# Power_supply.net
KiCad netlist of a schematic drawn in Altium Designer
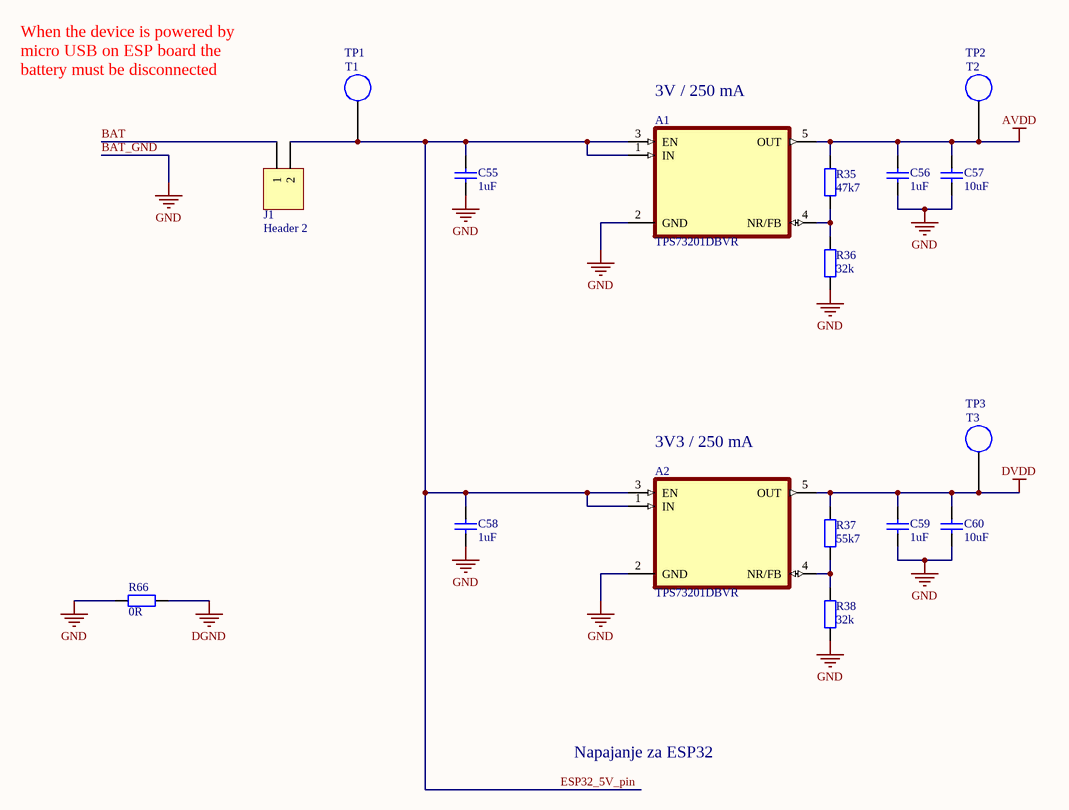
[diagram p0: Power supply.SchDoc]

(export (version "E")
  (design (tool "Eeschema 10.0.6"))
  (components
    (comp (ref "A1")
      (value "TPS73201DBVR")
      (footprint "SOT95P280X145-5N")
      (fields (field (name "MF") "Texas Instruments"))
      (libsource (lib "TPS73201DBVR") (part "TPS73201DBVR"))
    )
    (comp (ref "A2")
      (value "TPS73201DBVR")
      (footprint "SOT95P280X145-5N")
      (fields (field (name "MF") "Texas Instruments"))
      (libsource (lib "TPS73201DBVR") (part "TPS73201DBVR"))
    )
    (comp (ref "C55")
      (value "1uF")
      (footprint "C0603")
      (description "Capacitor")
      (fields (field (name "PUBLISHER") "Altium Limited"))
      (libsource (lib "Miscellaneous Devices") (part "Cap"))
    )
    (comp (ref "C56")
      (value "1uF")
      (footprint "C0603")
      (description "Capacitor")
      (fields (field (name "PUBLISHER") "Altium Limited"))
      (libsource (lib "Miscellaneous Devices") (part "Cap"))
    )
    (comp (ref "C57")
      (value "10uF")
      (footprint "C0603")
      (description "Capacitor")
      (fields (field (name "PUBLISHER") "Altium Limited"))
      (libsource (lib "Miscellaneous Devices") (part "Cap"))
    )
    (comp (ref "C58")
      (value "1uF")
      (footprint "C0603")
      (description "Capacitor")
      (fields (field (name "PUBLISHER") "Altium Limited"))
      (libsource (lib "Miscellaneous Devices") (part "Cap"))
    )
    (comp (ref "C59")
      (value "1uF")
      (footprint "C0603")
      (description "Capacitor")
      (fields (field (name "PUBLISHER") "Altium Limited"))
      (libsource (lib "Miscellaneous Devices") (part "Cap"))
    )
    (comp (ref "C60")
      (value "10uF")
      (footprint "C0603")
      (description "Capacitor")
      (fields (field (name "PUBLISHER") "Altium Limited"))
      (libsource (lib "Miscellaneous Devices") (part "Cap"))
    )
    (comp (ref "J1")
      (value "Header 2")
      (footprint "HDR1X2")
      (description "Header, 2-Pin")
      (fields (field (name "PUBLISHER") "Altium Limited"))
      (libsource (lib "Miscellaneous Connectors") (part "Header 2"))
    )
    (comp (ref "R35")
      (value "47k7")
      (footprint "RES0603")
      (description "Resistor")
      (fields (field (name "PUBLISHER") "Altium Limited"))
      (libsource (lib "Miscellaneous Devices") (part "Res2"))
    )
    (comp (ref "R36")
      (value "32k")
      (footprint "RES0603")
      (description "Resistor")
      (fields (field (name "PUBLISHER") "Altium Limited"))
      (libsource (lib "Miscellaneous Devices") (part "Res2"))
    )
    (comp (ref "R37")
      (value "55k7")
      (footprint "RES0603")
      (description "Resistor")
      (fields (field (name "PUBLISHER") "Altium Limited"))
      (libsource (lib "Miscellaneous Devices") (part "Res2"))
    )
    (comp (ref "R38")
      (value "32k")
      (footprint "RES0603")
      (description "Resistor")
      (fields (field (name "PUBLISHER") "Altium Limited"))
      (libsource (lib "Miscellaneous Devices") (part "Res2"))
    )
    (comp (ref "R66")
      (value "0R")
      (footprint "RES0603")
      (description "Resistor")
      (fields (field (name "PUBLISHER") "Altium Limited"))
      (libsource (lib "") (part "Res2_1"))
    )
    (comp (ref "T1") (value "TP1") (footprint "PCBComponent_1") (libsource (lib "Libs") (part "Component_1")))
    (comp (ref "T2") (value "TP2") (footprint "PCBComponent_1") (libsource (lib "Libs") (part "Component_1")))
    (comp (ref "T3") (value "TP3") (footprint "PCBComponent_1") (libsource (lib "Libs") (part "Component_1")))
  )
  (nets
    (net (code "1") (name "/BAT") (class "Default")
      (node (ref "J1") (pin "1") (pinfunction "1_1") (pintype "passive"))
    )
    (net (code "2") (name "/ESP32_5V_pin") (class "Default")
      (node (ref "A1") (pin "1") (pinfunction "IN_1") (pintype "input"))
      (node (ref "A1") (pin "3") (pinfunction "EN_3") (pintype "input"))
      (node (ref "A2") (pin "1") (pinfunction "IN_1") (pintype "input"))
      (node (ref "A2") (pin "3") (pinfunction "EN_3") (pintype "input"))
      (node (ref "C55") (pin "2") (pinfunction "2_2") (pintype "passive"))
      (node (ref "C58") (pin "2") (pinfunction "2_2") (pintype "passive"))
      (node (ref "J1") (pin "2") (pinfunction "2_2") (pintype "passive"))
      (node (ref "T1") (pin "1") (pinfunction "1_1") (pintype "passive"))
    )
    (net (code "3") (name "AVDD") (class "Default")
      (node (ref "A1") (pin "5") (pinfunction "OUT_5") (pintype "output"))
      (node (ref "C56") (pin "2") (pinfunction "2_2") (pintype "passive"))
      (node (ref "C57") (pin "2") (pinfunction "2_2") (pintype "passive"))
      (node (ref "R35") (pin "2") (pinfunction "2_2") (pintype "passive"))
      (node (ref "T2") (pin "1") (pinfunction "1_1") (pintype "passive"))
    )
    (net (code "4") (name "DGND") (class "Default")
      (node (ref "R66") (pin "1") (pinfunction "1_1") (pintype "passive"))
    )
    (net (code "5") (name "DVDD") (class "Default")
      (node (ref "A2") (pin "5") (pinfunction "OUT_5") (pintype "output"))
      (node (ref "C59") (pin "2") (pinfunction "2_2") (pintype "passive"))
      (node (ref "C60") (pin "2") (pinfunction "2_2") (pintype "passive"))
      (node (ref "R37") (pin "2") (pinfunction "2_2") (pintype "passive"))
      (node (ref "T3") (pin "1") (pinfunction "1_1") (pintype "passive"))
    )
    (net (code "6") (name "GND") (class "Default")
      (node (ref "A1") (pin "2") (pinfunction "GND_2") (pintype "power_in"))
      (node (ref "A2") (pin "2") (pinfunction "GND_2") (pintype "power_in"))
      (node (ref "C55") (pin "1") (pinfunction "1_1") (pintype "passive"))
      (node (ref "C56") (pin "1") (pinfunction "1_1") (pintype "passive"))
      (node (ref "C57") (pin "1") (pinfunction "1_1") (pintype "passive"))
      (node (ref "C58") (pin "1") (pinfunction "1_1") (pintype "passive"))
      (node (ref "C59") (pin "1") (pinfunction "1_1") (pintype "passive"))
      (node (ref "C60") (pin "1") (pinfunction "1_1") (pintype "passive"))
      (node (ref "R36") (pin "1") (pinfunction "1_1") (pintype "passive"))
      (node (ref "R38") (pin "1") (pinfunction "1_1") (pintype "passive"))
      (node (ref "R66") (pin "2") (pinfunction "2_2") (pintype "passive"))
    )
    (net (code "7") (name "Net-(A1-NR{slash}FB)") (class "Default")
      (node (ref "A1") (pin "4") (pinfunction "NR/FB_4") (pintype "bidirectional"))
      (node (ref "R35") (pin "1") (pinfunction "1_1") (pintype "passive"))
      (node (ref "R36") (pin "2") (pinfunction "2_2") (pintype "passive"))
    )
    (net (code "8") (name "Net-(A2-NR{slash}FB)") (class "Default")
      (node (ref "A2") (pin "4") (pinfunction "NR/FB_4") (pintype "bidirectional"))
      (node (ref "R37") (pin "1") (pinfunction "1_1") (pintype "passive"))
      (node (ref "R38") (pin "2") (pinfunction "2_2") (pintype "passive"))
    )
  )
)
